# thermal-flashlight.net
KiCad netlist of a schematic drawn in EAGLE
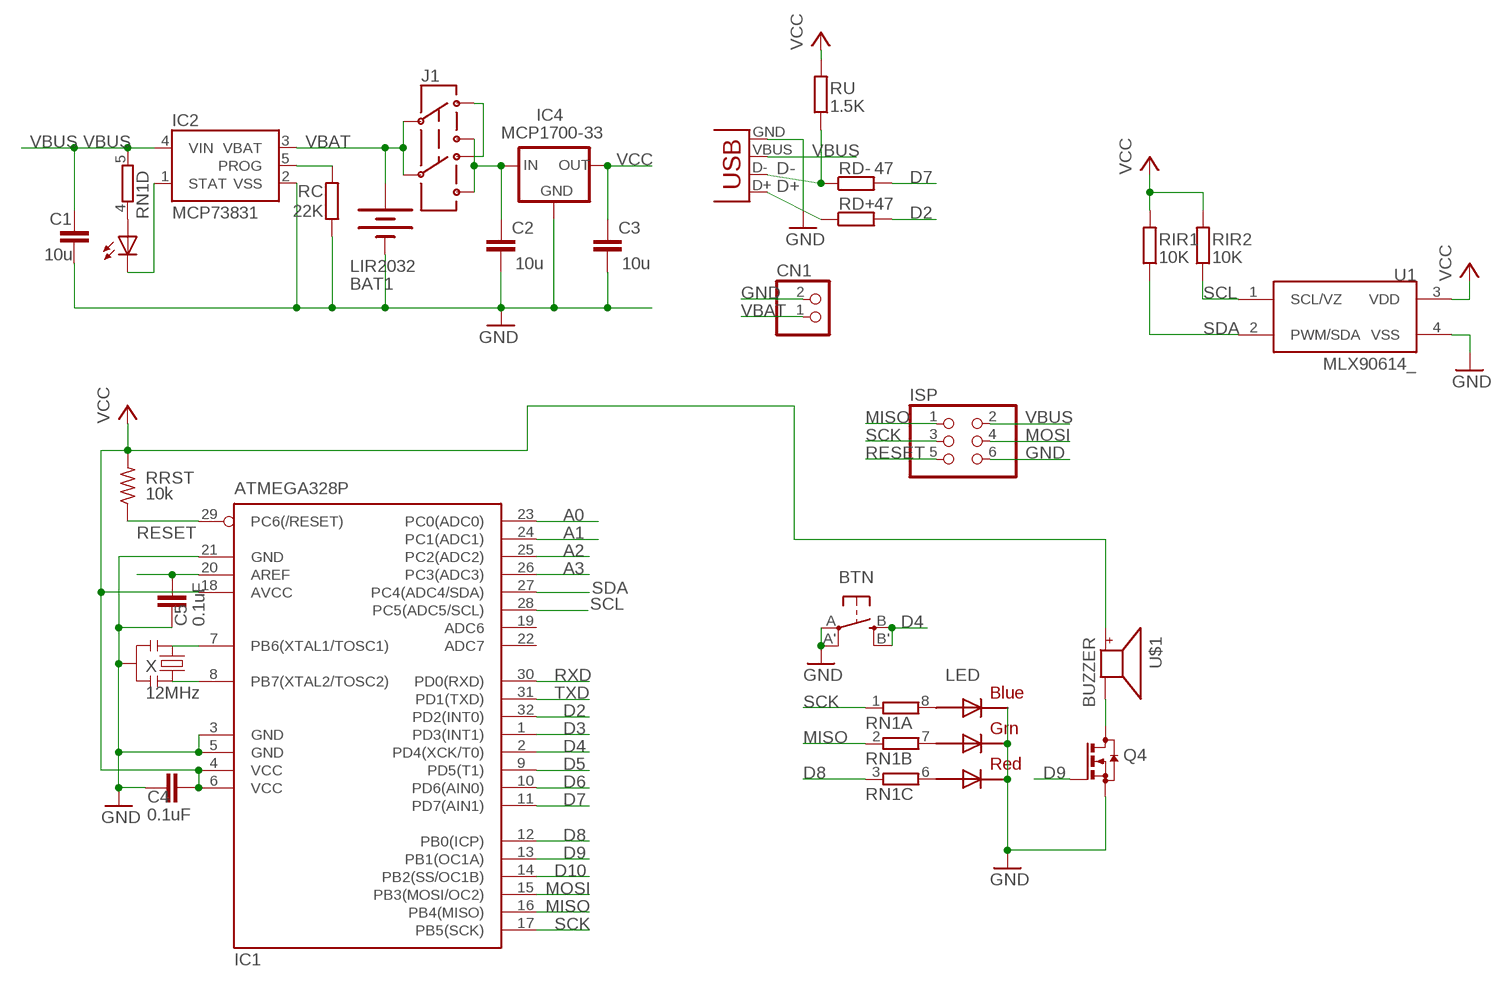
[diagram p0: schematic, sheet 1]

(export (version "E")
  (design (tool "Eeschema 10.0.6"))
  (components
    (comp (ref "BAT1")
      (value "LIR2032")
      (footprint "eagle-import:BATTCOM_20MM_PTH_SMT")
      (libsource (lib "eagle-import") (part "BATTERYBATTCOM_20MM_PTH_SMT"))
    )
    (comp (ref "BTN")
      (value "EVQQ2")
      (footprint "eagle-import:EVQ-Q2")
      (libsource (lib "eagle-import") (part "EVQQ2"))
    )
    (comp (ref "C1")
      (value "10u")
      (footprint "eagle-import:C0805")
      (libsource (lib "eagle-import") (part "resistor_C-EUC0805"))
    )
    (comp (ref "C2")
      (value "10u")
      (footprint "eagle-import:C0805")
      (libsource (lib "eagle-import") (part "resistor_C-EUC0805"))
    )
    (comp (ref "C3")
      (value "10u")
      (footprint "eagle-import:C0805")
      (libsource (lib "eagle-import") (part "resistor_C-EUC0805"))
    )
    (comp (ref "C4")
      (value "0.1uF")
      (footprint "eagle-import:C0805")
      (libsource (lib "eagle-import") (part "C-EUC0805"))
    )
    (comp (ref "C5")
      (value "0.1uF")
      (footprint "eagle-import:C0805")
      (libsource (lib "eagle-import") (part "C-EUC0805"))
    )
    (comp (ref "CHG")
      (value "0805")
      (footprint "eagle-import:CHIPLED_0805")
      (libsource (lib "eagle-import") (part "LEDCHIPLED_0805"))
    )
    (comp (ref "CN1")
      (value "JST_2PIN-SMT-RA")
      (footprint "eagle-import:JST-PH-2-SMT-RA")
      (libsource (lib "eagle-import") (part "JST_2PIN-SMT-RA"))
    )
    (comp (ref "IC1")
      (value "ATMEGA328P")
      (footprint "eagle-import:TQFP32-08")
      (fields (field (name "MPN") "ATMEGA8-16AU"))
      (libsource (lib "eagle-import") (part "MEGA8-AI"))
    )
    (comp (ref "IC2")
      (value "MCP73831")
      (footprint "eagle-import:SOT23-5")
      (libsource (lib "eagle-import") (part "MCP73831"))
    )
    (comp (ref "IC4")
      (value "MCP1700-33")
      (footprint "eagle-import:SOT23")
      (libsource (lib "eagle-import") (part "MCP1700SOT233"))
    )
    (comp (ref "ISP")
      (value "PINHD-2X3")
      (footprint "eagle-import:2X03")
      (libsource (lib "eagle-import") (part "PINHD-2X3"))
    )
    (comp (ref "J1")
      (value "AYZ0202")
      (footprint "eagle-import:AYZ0202")
      (libsource (lib "eagle-import") (part "AYZ0202"))
    )
    (comp (ref "LED")
      (value "RGBLED5050")
      (footprint "eagle-import:RGBLED5050")
      (libsource (lib "eagle-import") (part "RGBLED5050"))
    )
    (comp (ref "Q4")
      (value "BSS123")
      (footprint "eagle-import:SOT23")
      (libsource (lib "eagle-import") (part "BSS123"))
    )
    (comp (ref "RC")
      (value "22K")
      (footprint "eagle-import:R0805")
      (libsource (lib "eagle-import") (part "R-EU_R0805"))
    )
    (comp (ref "RD+")
      (value "47")
      (footprint "eagle-import:R0805")
      (libsource (lib "eagle-import") (part "R-EU_R0805"))
    )
    (comp (ref "RD-")
      (value "47")
      (footprint "eagle-import:R0805")
      (libsource (lib "eagle-import") (part "R-EU_R0805"))
    )
    (comp (ref "RIR1")
      (value "10K")
      (footprint "eagle-import:R0805")
      (libsource (lib "eagle-import") (part "R-EU_R0805"))
    )
    (comp (ref "RIR2")
      (value "10K")
      (footprint "eagle-import:R0805")
      (libsource (lib "eagle-import") (part "R-EU_R0805"))
    )
    (comp (ref "RN1")
      (value "4R-NEXB38V")
      (footprint "eagle-import:EXB38V")
      (libsource (lib "eagle-import") (part "4R-NEXB38V"))
    )
    (comp (ref "RRST")
      (value "10k")
      (footprint "eagle-import:R0805@1")
      (libsource (lib "eagle-import") (part "R-US_R0805"))
    )
    (comp (ref "RU")
      (value "1.5K")
      (footprint "eagle-import:R0805")
      (libsource (lib "eagle-import") (part "R-EU_R0805"))
    )
    (comp (ref "U$1")
      (value "BUZZER")
      (footprint "eagle-import:SMT-8585-BUZZER")
      (libsource (lib "eagle-import") (part "BUZZER"))
    )
    (comp (ref "U1")
      (value "MLX90614_")
      (footprint "eagle-import:TO-39")
      (libsource (lib "eagle-import") (part "MLX90614_"))
    )
    (comp (ref "X")
      (value "12MHz")
      (footprint "eagle-import:RESONATOR-SMD")
      (libsource (lib "eagle-import") (part "RESONATORSMD"))
    )
    (comp (ref "X1")
      (value "USBSMD")
      (footprint "eagle-import:USB-MINIB")
      (libsource (lib "eagle-import") (part "USBSMD"))
    )
  )
  (nets
    (net (code "1") (name "/A0") (class "Default")
      (node (ref "IC1") (pin "23") (pinfunction "PC0(ADC0)_23") (pintype "bidirectional"))
    )
    (net (code "2") (name "/A1") (class "Default")
      (node (ref "IC1") (pin "24") (pinfunction "PC1(ADC1)_24") (pintype "bidirectional"))
    )
    (net (code "3") (name "/A2") (class "Default")
      (node (ref "IC1") (pin "25") (pinfunction "PC2(ADC2)_25") (pintype "bidirectional"))
    )
    (net (code "4") (name "/A3") (class "Default")
      (node (ref "IC1") (pin "26") (pinfunction "PC3(ADC3)_26") (pintype "bidirectional"))
    )
    (net (code "5") (name "/D+") (class "Default")
      (node (ref "RD+") (pin "1") (pinfunction "1_1") (pintype "passive"))
      (node (ref "X1") (pin "D+") (pinfunction "D+_D+") (pintype "bidirectional"))
    )
    (net (code "6") (name "/D-") (class "Default")
      (node (ref "RD-") (pin "1") (pinfunction "1_1") (pintype "passive"))
      (node (ref "RU") (pin "1") (pinfunction "1_1") (pintype "passive"))
      (node (ref "X1") (pin "D-") (pinfunction "D-_D-") (pintype "bidirectional"))
    )
    (net (code "7") (name "/D2") (class "Default")
      (node (ref "IC1") (pin "32") (pinfunction "PD2(INT0)_32") (pintype "bidirectional"))
      (node (ref "RD+") (pin "2") (pinfunction "2_2") (pintype "passive"))
    )
    (net (code "8") (name "/D3") (class "Default")
      (node (ref "IC1") (pin "1") (pinfunction "PD3(INT1)_1") (pintype "bidirectional"))
    )
    (net (code "9") (name "/D4") (class "Default")
      (node (ref "BTN") (pin "B") (pinfunction "S_B") (pintype "passive"))
      (node (ref "BTN") (pin "B'") (pinfunction "S1_B'") (pintype "passive"))
      (node (ref "IC1") (pin "2") (pinfunction "PD4(XCK/T0)_2") (pintype "bidirectional"))
    )
    (net (code "10") (name "/D5") (class "Default")
      (node (ref "IC1") (pin "9") (pinfunction "PD5(T1)_9") (pintype "bidirectional"))
    )
    (net (code "11") (name "/D6") (class "Default")
      (node (ref "IC1") (pin "10") (pinfunction "PD6(AIN0)_10") (pintype "bidirectional"))
    )
    (net (code "12") (name "/D7") (class "Default")
      (node (ref "IC1") (pin "11") (pinfunction "PD7(AIN1)_11") (pintype "bidirectional"))
      (node (ref "RD-") (pin "2") (pinfunction "2_2") (pintype "passive"))
    )
    (net (code "13") (name "/D8") (class "Default")
      (node (ref "IC1") (pin "12") (pinfunction "PB0(ICP)_12") (pintype "bidirectional"))
      (node (ref "RN1") (pin "3") (pinfunction "1_3") (pintype "passive"))
    )
    (net (code "14") (name "/D9") (class "Default")
      (node (ref "IC1") (pin "13") (pinfunction "PB1(OC1A)_13") (pintype "bidirectional"))
      (node (ref "Q4") (pin "1") (pinfunction "G_1") (pintype "passive"))
    )
    (net (code "15") (name "/D10") (class "Default")
      (node (ref "IC1") (pin "14") (pinfunction "PB2(SS/OC1B)_14") (pintype "bidirectional"))
    )
    (net (code "16") (name "/MISO") (class "Default")
      (node (ref "IC1") (pin "16") (pinfunction "PB4(MISO)_16") (pintype "bidirectional"))
      (node (ref "ISP") (pin "1") (pinfunction "1_1") (pintype "passive"))
      (node (ref "RN1") (pin "2") (pinfunction "1_2") (pintype "passive"))
    )
    (net (code "17") (name "/MOSI") (class "Default")
      (node (ref "IC1") (pin "15") (pinfunction "PB3(MOSI/OC2)_15") (pintype "bidirectional"))
      (node (ref "ISP") (pin "4") (pinfunction "4_4") (pintype "passive"))
    )
    (net (code "18") (name "/RESET") (class "Default")
      (node (ref "IC1") (pin "29") (pinfunction "PC6(/RESET)_29") (pintype "bidirectional"))
      (node (ref "ISP") (pin "5") (pinfunction "5_5") (pintype "passive"))
      (node (ref "RRST") (pin "1") (pinfunction "1_1") (pintype "passive"))
    )
    (net (code "19") (name "/RXD") (class "Default")
      (node (ref "IC1") (pin "30") (pinfunction "PD0(RXD)_30") (pintype "bidirectional"))
    )
    (net (code "20") (name "/SCK") (class "Default")
      (node (ref "IC1") (pin "17") (pinfunction "PB5(SCK)_17") (pintype "bidirectional"))
      (node (ref "ISP") (pin "3") (pinfunction "3_3") (pintype "passive"))
      (node (ref "RN1") (pin "1") (pinfunction "1_1") (pintype "passive"))
    )
    (net (code "21") (name "/SCL") (class "Default")
      (node (ref "IC1") (pin "28") (pinfunction "PC5(ADC5/SCL)_28") (pintype "bidirectional"))
      (node (ref "RIR2") (pin "1") (pinfunction "1_1") (pintype "passive"))
      (node (ref "U1") (pin "1") (pinfunction "SCL/VZ_1") (pintype "bidirectional"))
    )
    (net (code "22") (name "/SDA") (class "Default")
      (node (ref "IC1") (pin "27") (pinfunction "PC4(ADC4/SDA)_27") (pintype "bidirectional"))
      (node (ref "RIR1") (pin "1") (pinfunction "1_1") (pintype "passive"))
      (node (ref "U1") (pin "2") (pinfunction "PWM/SDA_2") (pintype "bidirectional"))
    )
    (net (code "23") (name "/TXD") (class "Default")
      (node (ref "IC1") (pin "31") (pinfunction "PD1(TXD)_31") (pintype "bidirectional"))
    )
    (net (code "24") (name "/VBAT") (class "Default")
      (node (ref "BAT1") (pin "P$2") (pinfunction "+_P$2") (pintype "power_in"))
      (node (ref "CN1") (pin "1") (pinfunction "2_1") (pintype "passive"))
      (node (ref "IC2") (pin "3") (pinfunction "VBAT_3") (pintype "power_in"))
      (node (ref "J1") (pin "2") (pinfunction "2_2") (pintype "bidirectional"))
      (node (ref "J1") (pin "5") (pinfunction "5_5") (pintype "bidirectional"))
    )
    (net (code "25") (name "/VBUS") (class "Default")
      (node (ref "C1") (pin "1") (pinfunction "1_1") (pintype "passive"))
      (node (ref "IC2") (pin "4") (pinfunction "VIN_4") (pintype "power_in"))
      (node (ref "ISP") (pin "2") (pinfunction "2_2") (pintype "passive"))
      (node (ref "RN1") (pin "5") (pinfunction "2_5") (pintype "passive"))
      (node (ref "X1") (pin "VBUS") (pinfunction "VBUS_VBUS") (pintype "bidirectional"))
    )
    (net (code "26") (name "GND") (class "Default")
      (node (ref "BAT1") (pin "P$1") (pinfunction "-_P$1") (pintype "power_in"))
      (node (ref "BTN") (pin "A") (pinfunction "P_A") (pintype "passive"))
      (node (ref "BTN") (pin "A'") (pinfunction "P1_A'") (pintype "passive"))
      (node (ref "C1") (pin "2") (pinfunction "2_2") (pintype "passive"))
      (node (ref "C2") (pin "2") (pinfunction "2_2") (pintype "passive"))
      (node (ref "C3") (pin "2") (pinfunction "2_2") (pintype "passive"))
      (node (ref "C4") (pin "1") (pinfunction "1_1") (pintype "passive"))
      (node (ref "C5") (pin "1") (pinfunction "1_1") (pintype "passive"))
      (node (ref "CN1") (pin "2") (pinfunction "1_2") (pintype "passive"))
      (node (ref "IC1") (pin "21") (pinfunction "GND_21") (pintype "power_in"))
      (node (ref "IC1") (pin "3") (pinfunction "GND_3") (pintype "power_in"))
      (node (ref "IC1") (pin "5") (pinfunction "GND_5") (pintype "power_in"))
      (node (ref "IC2") (pin "2") (pinfunction "VSS_2") (pintype "power_in"))
      (node (ref "IC4") (pin "1") (pinfunction "GND_1") (pintype "input"))
      (node (ref "ISP") (pin "6") (pinfunction "6_6") (pintype "passive"))
      (node (ref "LED") (pin "4") (pinfunction "BLUE_C_4") (pintype "bidirectional"))
      (node (ref "LED") (pin "5") (pinfunction "RED_C_5") (pintype "bidirectional"))
      (node (ref "LED") (pin "6") (pinfunction "GREEN_C_6") (pintype "bidirectional"))
      (node (ref "Q4") (pin "2") (pinfunction "S_2") (pintype "passive"))
      (node (ref "RC") (pin "1") (pinfunction "1_1") (pintype "passive"))
      (node (ref "U1") (pin "4") (pinfunction "VSS_4") (pintype "bidirectional"))
      (node (ref "X") (pin "2") (pinfunction "2_2") (pintype "passive"))
      (node (ref "X1") (pin "GND") (pinfunction "GND_GND") (pintype "bidirectional"))
    )
    (net (code "27") (name "Net-(IC1-AREF)") (class "Default")
      (node (ref "C5") (pin "2") (pinfunction "2_2") (pintype "passive"))
      (node (ref "IC1") (pin "20") (pinfunction "AREF_20") (pintype "passive"))
    )
    (net (code "28") (name "Net-(IC1-PB6(XTAL1{slash}TOSC1))") (class "Default")
      (node (ref "IC1") (pin "7") (pinfunction "PB6(XTAL1/TOSC1)_7") (pintype "bidirectional"))
      (node (ref "X") (pin "1") (pinfunction "1_1") (pintype "passive"))
    )
    (net (code "29") (name "Net-(IC1-PB7(XTAL2{slash}TOSC2))") (class "Default")
      (node (ref "IC1") (pin "8") (pinfunction "PB7(XTAL2/TOSC2)_8") (pintype "bidirectional"))
      (node (ref "X") (pin "3") (pinfunction "3_3") (pintype "passive"))
    )
    (net (code "30") (name "Net-(IC2-PROG)") (class "Default")
      (node (ref "IC2") (pin "5") (pinfunction "PROG_5") (pintype "input"))
      (node (ref "RC") (pin "2") (pinfunction "2_2") (pintype "passive"))
    )
    (net (code "31") (name "Net-(IC2-STAT)") (class "Default")
      (node (ref "CHG") (pin "C") (pinfunction "C_C") (pintype "passive"))
      (node (ref "IC2") (pin "1") (pinfunction "STAT_1") (pintype "output"))
    )
    (net (code "32") (name "Net-(IC4-IN)") (class "Default")
      (node (ref "C2") (pin "1") (pinfunction "1_1") (pintype "passive"))
      (node (ref "IC4") (pin "3") (pinfunction "IN_3") (pintype "input"))
      (node (ref "J1") (pin "1") (pinfunction "3_1") (pintype "bidirectional"))
      (node (ref "J1") (pin "4") (pinfunction "6_4") (pintype "bidirectional"))
    )
    (net (code "33") (name "Net-(J1-1)") (class "Default")
      (node (ref "J1") (pin "3") (pinfunction "1_3") (pintype "bidirectional"))
      (node (ref "J1") (pin "6") (pinfunction "4_6") (pintype "bidirectional"))
    )
    (net (code "34") (name "Net-(LED-BLUE_A)") (class "Default")
      (node (ref "LED") (pin "3") (pinfunction "BLUE_A_3") (pintype "bidirectional"))
      (node (ref "RN1") (pin "8") (pinfunction "2_8") (pintype "passive"))
    )
    (net (code "35") (name "Net-(LED-GREEN_A)") (class "Default")
      (node (ref "LED") (pin "1") (pinfunction "GREEN_A_1") (pintype "bidirectional"))
      (node (ref "RN1") (pin "7") (pinfunction "2_7") (pintype "passive"))
    )
    (net (code "36") (name "Net-(LED-RED_A)") (class "Default")
      (node (ref "LED") (pin "2") (pinfunction "RED_A_2") (pintype "bidirectional"))
      (node (ref "RN1") (pin "6") (pinfunction "2_6") (pintype "passive"))
    )
    (net (code "37") (name "Net-(Q4-D)") (class "Default")
      (node (ref "Q4") (pin "3") (pinfunction "D_3") (pintype "passive"))
      (node (ref "U$1") (pin "-") (pinfunction "-_-") (pintype "passive"))
    )
    (net (code "38") (name "Net-(RN1D-1)") (class "Default")
      (node (ref "CHG") (pin "A") (pinfunction "A_A") (pintype "passive"))
      (node (ref "RN1") (pin "4") (pinfunction "1_4") (pintype "passive"))
    )
    (net (code "39") (name "VCC") (class "Default")
      (node (ref "C3") (pin "1") (pinfunction "1_1") (pintype "passive"))
      (node (ref "C4") (pin "2") (pinfunction "2_2") (pintype "passive"))
      (node (ref "IC1") (pin "18") (pinfunction "AVCC_18") (pintype "power_in"))
      (node (ref "IC1") (pin "4") (pinfunction "VCC_4") (pintype "power_in"))
      (node (ref "IC1") (pin "6") (pinfunction "VCC_6") (pintype "power_in"))
      (node (ref "IC4") (pin "2") (pinfunction "OUT_2") (pintype "passive"))
      (node (ref "RIR1") (pin "2") (pinfunction "2_2") (pintype "passive"))
      (node (ref "RIR2") (pin "2") (pinfunction "2_2") (pintype "passive"))
      (node (ref "RRST") (pin "2") (pinfunction "2_2") (pintype "passive"))
      (node (ref "RU") (pin "2") (pinfunction "2_2") (pintype "passive"))
      (node (ref "U$1") (pin "+") (pinfunction "+_+") (pintype "passive"))
      (node (ref "U1") (pin "3") (pinfunction "VDD_3") (pintype "bidirectional"))
    )
    (net (code "40") (name "unconnected-(IC1-ADC6-Pad19)") (class "Default")
      (node (ref "IC1") (pin "19") (pinfunction "ADC6_19") (pintype "bidirectional"))
    )
    (net (code "41") (name "unconnected-(IC1-ADC7-Pad22)") (class "Default")
      (node (ref "IC1") (pin "22") (pinfunction "ADC7_22") (pintype "bidirectional"))
    )
  )
)
